# MAIN.net
KiCad netlist of a schematic drawn in Altium Designer
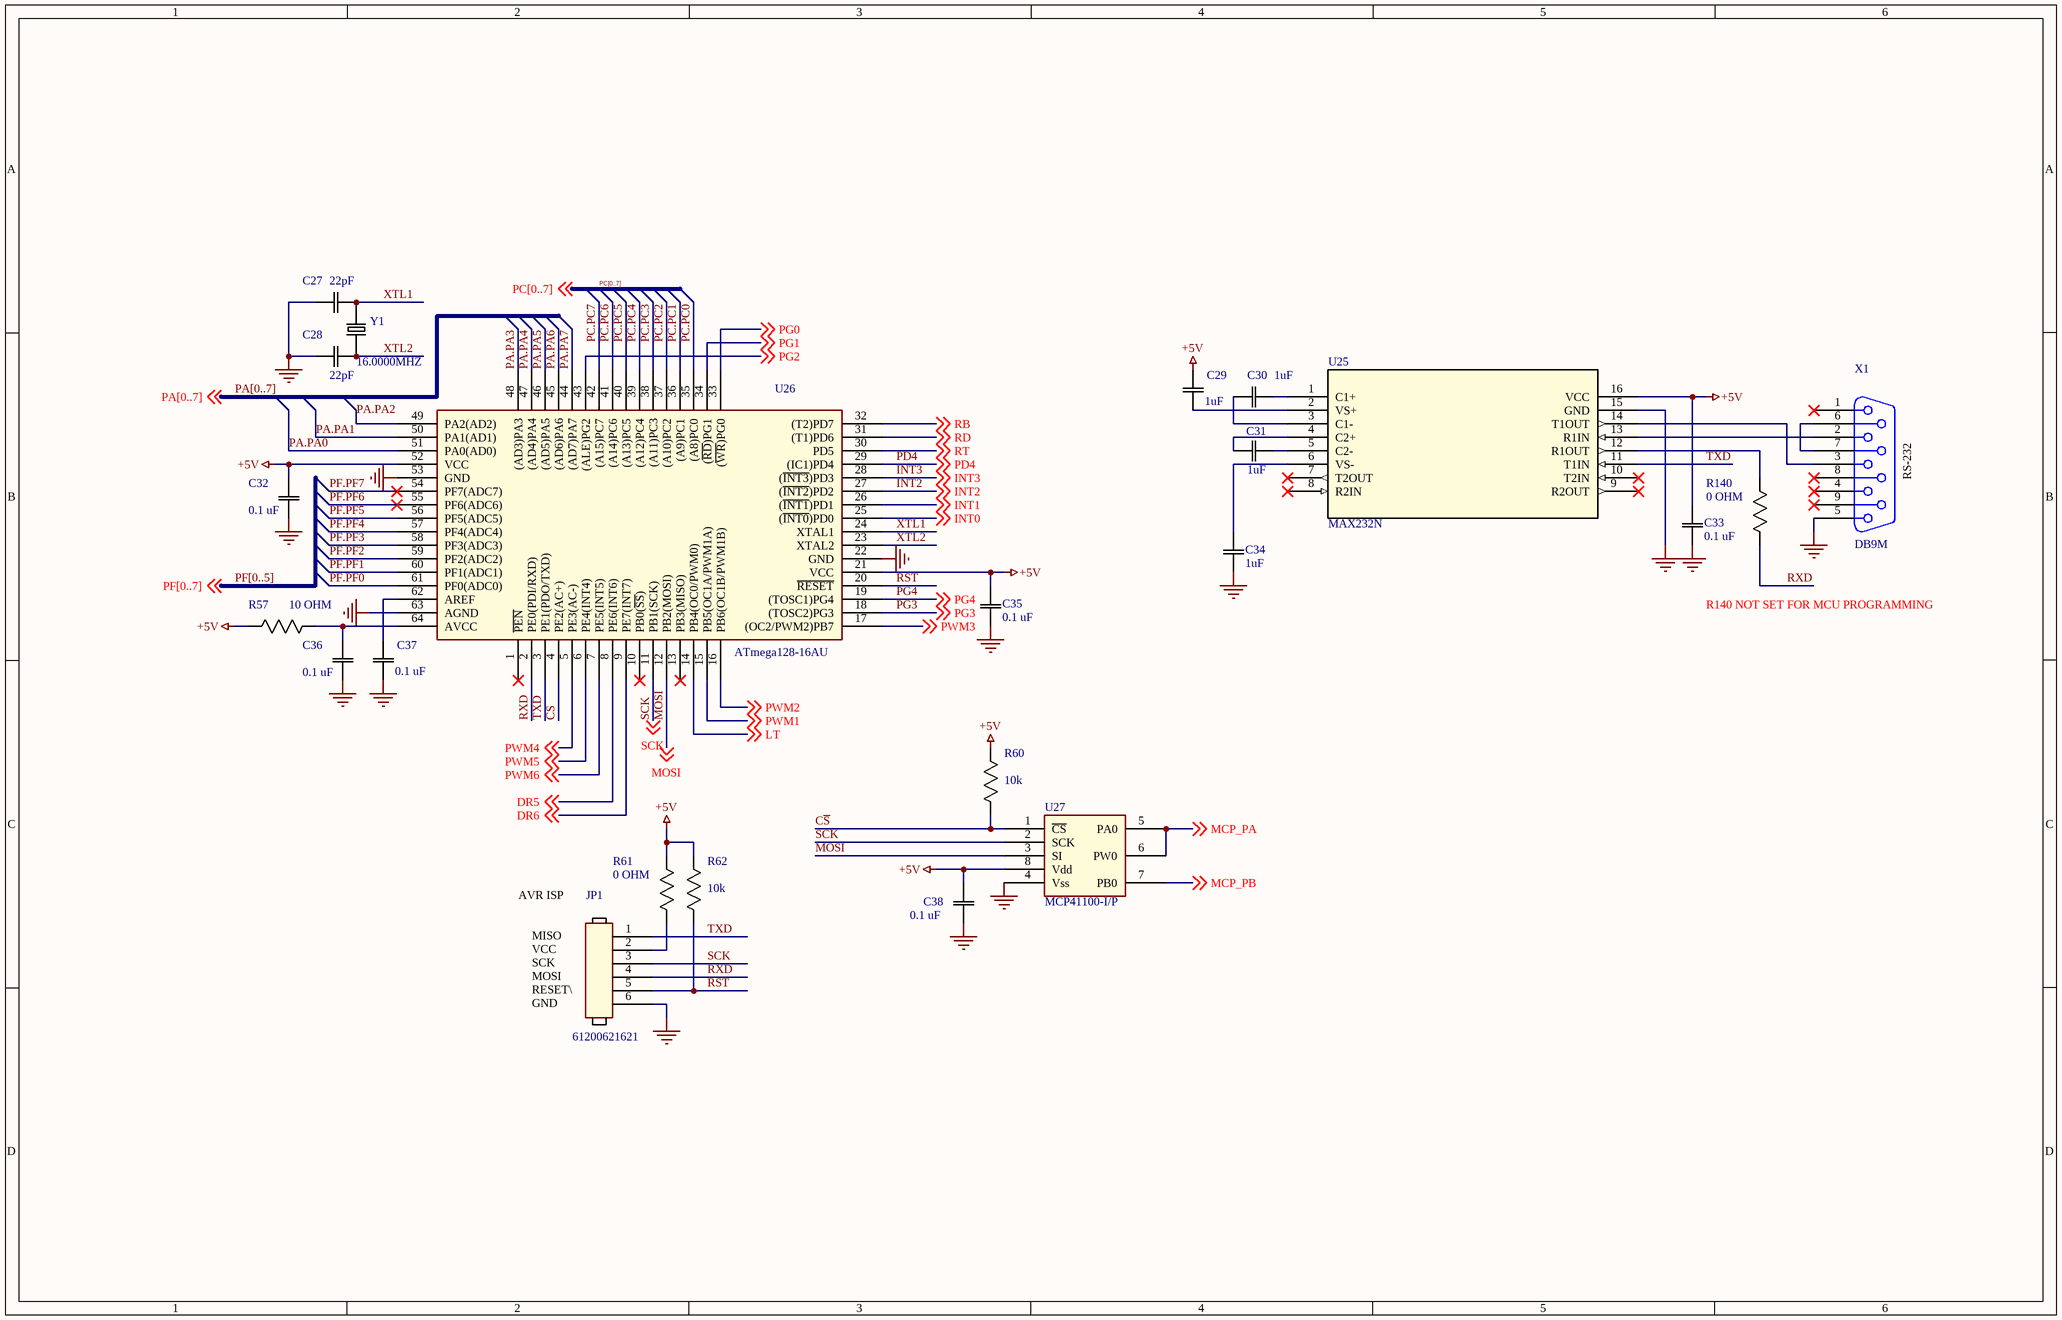
[diagram p0: MAIN.SchDoc]

(export (version "E")
  (design (tool "Eeschema 10.0.6"))
  (components
    (comp (ref "C27")
      (value "22pF")
      (footprint "SR20")
      (description "22pF ±5% 50V Ceramic Capacitor C0G, NP0 Radial")
      (fields (field (name "MANUFACTURER_PART_NUMBER") "C315C220J5G5TA"))
      (libsource (lib "Discrete") (part "CAP RADIAL 2.54"))
    )
    (comp (ref "C28")
      (value "22pF")
      (footprint "SR20")
      (description "22pF ±5% 50V Ceramic Capacitor C0G, NP0 Radial")
      (fields (field (name "MANUFACTURER_PART_NUMBER") "C315C220J5G5TA"))
      (libsource (lib "Discrete") (part "CAP RADIAL 2.54"))
    )
    (comp (ref "C29")
      (value "1uF")
      (footprint "SR20")
      (description "1µF ±10% 25V Ceramic Capacitor X7R Radial")
      (fields (field (name "MANUFACTURER_PART_NUMBER") "C315C105K3R5TA"))
      (libsource (lib "Discrete") (part "CAP RADIAL 2.54"))
    )
    (comp (ref "C30")
      (value "1uF")
      (footprint "SR20")
      (description "1µF ±10% 25V Ceramic Capacitor X7R Radial")
      (fields (field (name "MANUFACTURER_PART_NUMBER") "C315C105K3R5TA"))
      (libsource (lib "Discrete") (part "CAP RADIAL 2.54"))
    )
    (comp (ref "C31")
      (value "1uF")
      (footprint "SR20")
      (description "1µF ±10% 25V Ceramic Capacitor X7R Radial")
      (fields (field (name "MANUFACTURER_PART_NUMBER") "C315C105K3R5TA"))
      (libsource (lib "Discrete") (part "CAP RADIAL 2.54"))
    )
    (comp (ref "C32")
      (value "0.1 uF")
      (footprint "SR20")
      (description "0.1µF ±10% 100V Ceramic Capacitor X7R Radial")
      (fields (field (name "MANUFACTURER_PART_NUMBER") "C320C104K1R5TA7301"))
      (libsource (lib "Discrete") (part "CAP RADIAL 2.54"))
    )
    (comp (ref "C33")
      (value "0.1 uF")
      (footprint "SR20")
      (description "0.1µF ±10% 100V Ceramic Capacitor X7R Radial")
      (fields (field (name "MANUFACTURER_PART_NUMBER") "C320C104K1R5TA7301"))
      (libsource (lib "Discrete") (part "CAP RADIAL 2.54"))
    )
    (comp (ref "C34")
      (value "1uF")
      (footprint "SR20")
      (description "1µF ±10% 25V Ceramic Capacitor X7R Radial")
      (fields (field (name "MANUFACTURER_PART_NUMBER") "C315C105K3R5TA"))
      (libsource (lib "Discrete") (part "CAP RADIAL 2.54"))
    )
    (comp (ref "C35")
      (value "0.1 uF")
      (footprint "SR20")
      (description "0.1µF ±10% 100V Ceramic Capacitor X7R Radial")
      (fields (field (name "MANUFACTURER_PART_NUMBER") "C320C104K1R5TA7301"))
      (libsource (lib "Discrete") (part "CAP RADIAL 2.54"))
    )
    (comp (ref "C36")
      (value "0.1 uF")
      (footprint "SR20")
      (description "0.1µF ±10% 100V Ceramic Capacitor X7R Radial")
      (fields (field (name "MANUFACTURER_PART_NUMBER") "C320C104K1R5TA7301"))
      (libsource (lib "Discrete") (part "CAP RADIAL 2.54"))
    )
    (comp (ref "C37")
      (value "0.1 uF")
      (footprint "SR20")
      (description "0.1µF ±10% 100V Ceramic Capacitor X7R Radial")
      (fields (field (name "MANUFACTURER_PART_NUMBER") "C320C104K1R5TA7301"))
      (libsource (lib "Discrete") (part "CAP RADIAL 2.54"))
    )
    (comp (ref "C38")
      (value "0.1 uF")
      (footprint "SR20")
      (description "0.1µF ±10% 100V Ceramic Capacitor X7R Radial")
      (fields (field (name "MANUFACTURER_PART_NUMBER") "C320C104K1R5TA7301"))
      (libsource (lib "Discrete") (part "CAP RADIAL 2.54"))
    )
    (comp (ref "JP1")
      (value "61200621621")
      (footprint "BLKCON.100/VH/TM2OE/W.200/6")
      (description "Wire-To-Board Connector, WR-BHD Series, Through Hole, Header, 6, 2.54 mm, Gold Plated Contacts")
      (libsource (lib "*") (part "HEADER 6"))
    )
    (comp (ref "R57")
      (value "10 OHM")
      (footprint "RES AXIAL 1/6W")
      (description "RES 10 OHM 1/6W 5% AXIAL")
      (fields (field (name "MANUFACTURER_PART_NUMBER") "CFR-12JB-52-10R"))
      (libsource (lib "Discrete") (part "Resistor Axial  1/6W"))
    )
    (comp (ref "R60")
      (value "10k")
      (footprint "RES AXIAL 1/6W")
      (description "RES 10K OHM 1/6W 5% AXIAL")
      (fields (field (name "MANUFACTURER_PART_NUMBER") "CFR-12JB-52-10K"))
      (libsource (lib "Discrete") (part "Resistor Axial  1/6W"))
    )
    (comp (ref "R61")
      (value "0 OHM")
      (footprint "RES AXIAL 1/6W")
      (description "RES 0 OHM 1/6W JUMP AXIAL")
      (fields (field (name "MANUFACTURER_PART_NUMBER") "ZOR-12-B-52-0R"))
      (libsource (lib "Discrete") (part "Resistor Axial  1/6W"))
    )
    (comp (ref "R62")
      (value "10k")
      (footprint "RES AXIAL 1/6W")
      (description "RES 10K OHM 1/6W 5% AXIAL")
      (fields (field (name "MANUFACTURER_PART_NUMBER") "CFR-12JB-52-10K"))
      (libsource (lib "Discrete") (part "Resistor Axial  1/6W"))
    )
    (comp (ref "R140")
      (value "0 OHM")
      (footprint "RES AXIAL 1/6W")
      (description "RES 0 OHM 1/6W JUMP AXIAL")
      (fields (field (name "MANUFACTURER_PART_NUMBER") "ZOR-12-B-52-0R"))
      (libsource (lib "Discrete") (part "Resistor Axial  1/6W"))
    )
    (comp (ref "U25")
      (value "MAX232N")
      (footprint "N16")
      (description "Imported")
      (libsource (lib "ICs") (part "MAX232N"))
    )
    (comp (ref "U26")
      (value "ATmega128-16AU")
      (footprint "QUAD.80M/64/WG16.00")
      (libsource (lib "*") (part "ATMega103_1"))
    )
    (comp (ref "U27")
      (value "MCP41100-I/P")
      (footprint "*DIP254P762X508-8")
      (description "IC POT DGTL 100K 2CH SPI 14-DIP")
      (libsource (lib "ICs") (part "MCP41100-I/P"))
    )
    (comp (ref "X1")
      (value "DB9M")
      (footprint "DSUB/RP.318/TM/9")
      (libsource (lib "*") (part "CONNECTOR DB9"))
    )
    (comp (ref "Y1")
      (value "16.0000MHZ")
      (footprint "HC-49/US")
      (description "16MHz ±30ppm Crystal 20pF 40 Ohms HC-49/US")
      (fields (field (name "MANUFACTURER_PART_NUMBER") "ECS-160-20-4X"))
      (libsource (lib "Discrete") (part "CRYSTAL HC-49/US"))
    )
  )
  (nets
    (net (code "1") (name "+5V") (class "Default")
      (node (ref "C29") (pin "1") (pinfunction "1_1") (pintype "passive"))
      (node (ref "C32") (pin "2") (pinfunction "2_2") (pintype "passive"))
      (node (ref "C33") (pin "2") (pinfunction "2_2") (pintype "passive"))
      (node (ref "C35") (pin "2") (pinfunction "2_2") (pintype "passive"))
      (node (ref "C38") (pin "2") (pinfunction "2_2") (pintype "passive"))
      (node (ref "R57") (pin "2") (pinfunction "2_2") (pintype "passive"))
      (node (ref "R60") (pin "2") (pinfunction "2_2") (pintype "passive"))
      (node (ref "R61") (pin "2") (pinfunction "2_2") (pintype "passive"))
      (node (ref "R62") (pin "2") (pinfunction "2_2") (pintype "passive"))
      (node (ref "U25") (pin "16") (pinfunction "VCC_16") (pintype "power_in"))
      (node (ref "U26") (pin "21") (pinfunction "VCC_21") (pintype "power_in"))
      (node (ref "U26") (pin "52") (pinfunction "VCC_52") (pintype "power_in"))
      (node (ref "U27") (pin "8") (pinfunction "Vdd_8") (pintype "passive"))
    )
    (net (code "2") (name "/C~{S}") (class "Default")
      (node (ref "R60") (pin "1") (pinfunction "1_1") (pintype "passive"))
      (node (ref "U26") (pin "4") (pinfunction "PE2(AC+)_4") (pintype "passive"))
      (node (ref "U27") (pin "1") (pinfunction "~{CS}_1") (pintype "passive"))
    )
    (net (code "3") (name "/PA.PA0") (class "Default")
      (node (ref "U26") (pin "51") (pinfunction "PA0(AD0)_51") (pintype "passive"))
    )
    (net (code "4") (name "/PA.PA1") (class "Default")
      (node (ref "U26") (pin "50") (pinfunction "PA1(AD1)_50") (pintype "passive"))
    )
    (net (code "5") (name "/PA.PA2") (class "Default")
      (node (ref "U26") (pin "49") (pinfunction "PA2(AD2)_49") (pintype "passive"))
    )
    (net (code "6") (name "/PA.PA3") (class "Default")
      (node (ref "U26") (pin "48") (pinfunction "(AD3)PA3_48") (pintype "passive"))
    )
    (net (code "7") (name "/PA.PA4") (class "Default")
      (node (ref "U26") (pin "47") (pinfunction "(AD4)PA4_47") (pintype "passive"))
    )
    (net (code "8") (name "/PA.PA5") (class "Default")
      (node (ref "U26") (pin "46") (pinfunction "(AD5)PA5_46") (pintype "passive"))
    )
    (net (code "9") (name "/PA.PA6") (class "Default")
      (node (ref "U26") (pin "45") (pinfunction "(AD6)PA6_45") (pintype "passive"))
    )
    (net (code "10") (name "/PA.PA7") (class "Default")
      (node (ref "U26") (pin "44") (pinfunction "(AD7)PA7_44") (pintype "passive"))
    )
    (net (code "11") (name "/PC.PC0") (class "Default")
      (node (ref "U26") (pin "35") (pinfunction "(A8)PC0_35") (pintype "passive"))
    )
    (net (code "12") (name "/PC.PC1") (class "Default")
      (node (ref "U26") (pin "36") (pinfunction "(A9)PC1_36") (pintype "passive"))
    )
    (net (code "13") (name "/PC.PC2") (class "Default")
      (node (ref "U26") (pin "37") (pinfunction "(A10)PC2_37") (pintype "passive"))
    )
    (net (code "14") (name "/PC.PC3") (class "Default")
      (node (ref "U26") (pin "38") (pinfunction "(A11)PC3_38") (pintype "passive"))
    )
    (net (code "15") (name "/PC.PC4") (class "Default")
      (node (ref "U26") (pin "39") (pinfunction "(A12)PC4_39") (pintype "passive"))
    )
    (net (code "16") (name "/PC.PC5") (class "Default")
      (node (ref "U26") (pin "40") (pinfunction "(A13)PC5_40") (pintype "passive"))
    )
    (net (code "17") (name "/PC.PC6") (class "Default")
      (node (ref "U26") (pin "41") (pinfunction "(A14)PC6_41") (pintype "passive"))
    )
    (net (code "18") (name "/PC.PC7") (class "Default")
      (node (ref "U26") (pin "42") (pinfunction "(A15)PC7_42") (pintype "passive"))
    )
    (net (code "19") (name "/PF.PF0") (class "Default")
      (node (ref "U26") (pin "61") (pinfunction "PF0(ADC0)_61") (pintype "passive"))
    )
    (net (code "20") (name "/PF.PF1") (class "Default")
      (node (ref "U26") (pin "60") (pinfunction "PF1(ADC1)_60") (pintype "passive"))
    )
    (net (code "21") (name "/PF.PF2") (class "Default")
      (node (ref "U26") (pin "59") (pinfunction "PF2(ADC2)_59") (pintype "passive"))
    )
    (net (code "22") (name "/PF.PF3") (class "Default")
      (node (ref "U26") (pin "58") (pinfunction "PF3(ADC3)_58") (pintype "passive"))
    )
    (net (code "23") (name "/PF.PF4") (class "Default")
      (node (ref "U26") (pin "57") (pinfunction "PF4(ADC4)_57") (pintype "passive"))
    )
    (net (code "24") (name "/PF.PF5") (class "Default")
      (node (ref "U26") (pin "56") (pinfunction "PF5(ADC5)_56") (pintype "passive"))
    )
    (net (code "25") (name "/PF.PF6") (class "Default")
      (node (ref "U26") (pin "55") (pinfunction "PF6(ADC6)_55") (pintype "passive+no_connect"))
    )
    (net (code "26") (name "/PF.PF7") (class "Default")
      (node (ref "U26") (pin "54") (pinfunction "PF7(ADC7)_54") (pintype "passive+no_connect"))
    )
    (net (code "27") (name "/RS~{T}") (class "Default")
      (node (ref "JP1") (pin "5") (pinfunction "5_5") (pintype "passive"))
      (node (ref "R62") (pin "1") (pinfunction "1_1") (pintype "passive"))
      (node (ref "U26") (pin "20") (pinfunction "~{RESET}_20") (pintype "passive"))
    )
    (net (code "28") (name "/RXD") (class "Default")
      (node (ref "JP1") (pin "4") (pinfunction "4_4") (pintype "passive"))
      (node (ref "R140") (pin "1") (pinfunction "1_1") (pintype "passive"))
      (node (ref "U26") (pin "2") (pinfunction "PE0(PDI/RXD)_2") (pintype "passive"))
    )
    (net (code "29") (name "/TXD") (class "Default")
      (node (ref "JP1") (pin "1") (pinfunction "1_1") (pintype "passive"))
      (node (ref "U25") (pin "11") (pinfunction "T1IN_11") (pintype "input"))
      (node (ref "U26") (pin "3") (pinfunction "PE1(PDO/TXD)_3") (pintype "passive"))
    )
    (net (code "30") (name "/XTL1") (class "Default")
      (node (ref "C27") (pin "2") (pinfunction "2_2") (pintype "passive"))
      (node (ref "U26") (pin "24") (pinfunction "XTAL1_24") (pintype "passive"))
      (node (ref "Y1") (pin "1") (pinfunction "1_1") (pintype "passive"))
    )
    (net (code "31") (name "/XTL2") (class "Default")
      (node (ref "C28") (pin "2") (pinfunction "2_2") (pintype "passive"))
      (node (ref "U26") (pin "23") (pinfunction "XTAL2_23") (pintype "passive"))
      (node (ref "Y1") (pin "2") (pinfunction "2_2") (pintype "passive"))
    )
    (net (code "32") (name "DR5") (class "Default")
      (node (ref "U26") (pin "8") (pinfunction "PE6(INT6)_8") (pintype "passive"))
    )
    (net (code "33") (name "DR6") (class "Default")
      (node (ref "U26") (pin "9") (pinfunction "PE7(INT7)_9") (pintype "passive"))
    )
    (net (code "34") (name "GND") (class "Default")
      (node (ref "C27") (pin "1") (pinfunction "1_1") (pintype "passive"))
      (node (ref "C28") (pin "1") (pinfunction "1_1") (pintype "passive"))
      (node (ref "C32") (pin "1") (pinfunction "1_1") (pintype "passive"))
      (node (ref "C33") (pin "1") (pinfunction "1_1") (pintype "passive"))
      (node (ref "C34") (pin "2") (pinfunction "2_2") (pintype "passive"))
      (node (ref "C35") (pin "1") (pinfunction "1_1") (pintype "passive"))
      (node (ref "C36") (pin "1") (pinfunction "1_1") (pintype "passive"))
      (node (ref "C37") (pin "1") (pinfunction "1_1") (pintype "passive"))
      (node (ref "C38") (pin "1") (pinfunction "1_1") (pintype "passive"))
      (node (ref "JP1") (pin "6") (pinfunction "6_6") (pintype "passive"))
      (node (ref "U25") (pin "15") (pinfunction "GND_15") (pintype "power_in"))
      (node (ref "U26") (pin "22") (pinfunction "GND_22") (pintype "power_in"))
      (node (ref "U26") (pin "53") (pinfunction "GND_53") (pintype "power_in"))
      (node (ref "U26") (pin "63") (pinfunction "AGND_63") (pintype "passive"))
      (node (ref "U27") (pin "4") (pinfunction "Vss_4") (pintype "passive"))
      (node (ref "X1") (pin "5") (pinfunction "5_5") (pintype "passive"))
    )
    (net (code "35") (name "INT0") (class "Default")
      (node (ref "U26") (pin "25") (pinfunction "(~{INT0})PD0_25") (pintype "passive"))
    )
    (net (code "36") (name "INT1") (class "Default")
      (node (ref "U26") (pin "26") (pinfunction "(~{INT1})PD1_26") (pintype "passive"))
    )
    (net (code "37") (name "INT2") (class "Default")
      (node (ref "U26") (pin "27") (pinfunction "(~{INT2})PD2_27") (pintype "passive"))
    )
    (net (code "38") (name "INT3") (class "Default")
      (node (ref "U26") (pin "28") (pinfunction "(~{INT3})PD3_28") (pintype "passive"))
    )
    (net (code "39") (name "LT") (class "Default")
      (node (ref "U26") (pin "14") (pinfunction "PB4(OC0/PWM0)_14") (pintype "passive"))
    )
    (net (code "40") (name "MCP_PA") (class "Default")
      (node (ref "U27") (pin "5") (pinfunction "PA0_5") (pintype "passive"))
      (node (ref "U27") (pin "6") (pinfunction "PW0_6") (pintype "passive"))
    )
    (net (code "41") (name "MCP_PB") (class "Default")
      (node (ref "U27") (pin "7") (pinfunction "PB0_7") (pintype "passive"))
    )
    (net (code "42") (name "MOSI") (class "Default")
      (node (ref "U26") (pin "12") (pinfunction "PB2(MOSI)_12") (pintype "passive"))
      (node (ref "U27") (pin "3") (pinfunction "SI_3") (pintype "passive"))
    )
    (net (code "43") (name "Net-(JP1-Pad2)") (class "Default")
      (node (ref "JP1") (pin "2") (pinfunction "2_2") (pintype "passive"))
      (node (ref "R61") (pin "1") (pinfunction "1_1") (pintype "passive"))
    )
    (net (code "44") (name "Net-(U25-C1+)") (class "Default")
      (node (ref "C30") (pin "1") (pinfunction "1_1") (pintype "passive"))
      (node (ref "U25") (pin "1") (pinfunction "C1+_1") (pintype "passive"))
    )
    (net (code "45") (name "Net-(U25-C1-)") (class "Default")
      (node (ref "C30") (pin "2") (pinfunction "2_2") (pintype "passive"))
      (node (ref "U25") (pin "3") (pinfunction "C1-_3") (pintype "passive"))
    )
    (net (code "46") (name "Net-(U25-C2+)") (class "Default")
      (node (ref "C31") (pin "2") (pinfunction "2_2") (pintype "passive"))
      (node (ref "U25") (pin "4") (pinfunction "C2+_4") (pintype "passive"))
    )
    (net (code "47") (name "Net-(U25-C2-)") (class "Default")
      (node (ref "C31") (pin "1") (pinfunction "1_1") (pintype "passive"))
      (node (ref "U25") (pin "5") (pinfunction "C2-_5") (pintype "passive"))
    )
    (net (code "48") (name "Net-(U25-R1IN)") (class "Default")
      (node (ref "U25") (pin "13") (pinfunction "R1IN_13") (pintype "input"))
      (node (ref "X1") (pin "2") (pinfunction "2_2") (pintype "passive"))
    )
    (net (code "49") (name "Net-(U25-R1OUT)") (class "Default")
      (node (ref "R140") (pin "2") (pinfunction "2_2") (pintype "passive"))
      (node (ref "U25") (pin "12") (pinfunction "R1OUT_12") (pintype "output"))
    )
    (net (code "50") (name "Net-(U25-T1OUT)") (class "Default")
      (node (ref "U25") (pin "14") (pinfunction "T1OUT_14") (pintype "output"))
      (node (ref "X1") (pin "3") (pinfunction "3_3") (pintype "passive"))
    )
    (net (code "51") (name "Net-(U25-VS+)") (class "Default")
      (node (ref "C29") (pin "2") (pinfunction "2_2") (pintype "passive"))
      (node (ref "U25") (pin "2") (pinfunction "VS+_2") (pintype "power_in"))
    )
    (net (code "52") (name "Net-(U25-VS-)") (class "Default")
      (node (ref "C34") (pin "1") (pinfunction "1_1") (pintype "passive"))
      (node (ref "U25") (pin "6") (pinfunction "VS-_6") (pintype "power_in"))
    )
    (net (code "53") (name "Net-(U26-AREF)") (class "Default")
      (node (ref "C37") (pin "2") (pinfunction "2_2") (pintype "passive"))
      (node (ref "U26") (pin "62") (pinfunction "AREF_62") (pintype "passive"))
    )
    (net (code "54") (name "Net-(U26-AVCC)") (class "Default")
      (node (ref "C36") (pin "2") (pinfunction "2_2") (pintype "passive"))
      (node (ref "R57") (pin "1") (pinfunction "1_1") (pintype "passive"))
      (node (ref "U26") (pin "64") (pinfunction "AVCC_64") (pintype "passive"))
    )
    (net (code "55") (name "Net-(X1-Pad6)") (class "Default")
      (node (ref "X1") (pin "6") (pinfunction "6_6") (pintype "passive"))
      (node (ref "X1") (pin "7") (pinfunction "7_7") (pintype "passive"))
    )
    (net (code "58") (name "PD4") (class "Default")
      (node (ref "U26") (pin "29") (pinfunction "(IC1)PD4_29") (pintype "passive"))
    )
    (net (code "60") (name "PG0") (class "Default")
      (node (ref "U26") (pin "33") (pinfunction "(~{WR})PG0_33") (pintype "passive"))
    )
    (net (code "61") (name "PG1") (class "Default")
      (node (ref "U26") (pin "34") (pinfunction "(~{RD})PG1_34") (pintype "passive"))
    )
    (net (code "62") (name "PG2") (class "Default")
      (node (ref "U26") (pin "43") (pinfunction "(ALE)PG2_43") (pintype "passive"))
    )
    (net (code "63") (name "PG3") (class "Default")
      (node (ref "U26") (pin "18") (pinfunction "(TOSC2)PG3_18") (pintype "passive"))
    )
    (net (code "64") (name "PG4") (class "Default")
      (node (ref "U26") (pin "19") (pinfunction "(TOSC1)PG4_19") (pintype "passive"))
    )
    (net (code "65") (name "PWM1") (class "Default")
      (node (ref "U26") (pin "15") (pinfunction "PB5(OC1A/PWM1A)_15") (pintype "passive"))
    )
    (net (code "66") (name "PWM2") (class "Default")
      (node (ref "U26") (pin "16") (pinfunction "PB6(OC1B/PWM1B)_16") (pintype "passive"))
    )
    (net (code "67") (name "PWM3") (class "Default")
      (node (ref "U26") (pin "17") (pinfunction "(OC2/PWM2)PB7_17") (pintype "passive"))
    )
    (net (code "68") (name "PWM4") (class "Default")
      (node (ref "U26") (pin "5") (pinfunction "PE3(AC-)_5") (pintype "passive"))
    )
    (net (code "69") (name "PWM5") (class "Default")
      (node (ref "U26") (pin "6") (pinfunction "PE4(INT4)_6") (pintype "passive"))
    )
    (net (code "70") (name "PWM6") (class "Default")
      (node (ref "U26") (pin "7") (pinfunction "PE5(INT5)_7") (pintype "passive"))
    )
    (net (code "71") (name "RB") (class "Default")
      (node (ref "U26") (pin "32") (pinfunction "(T2)PD7_32") (pintype "passive"))
    )
    (net (code "72") (name "RD") (class "Default")
      (node (ref "U26") (pin "31") (pinfunction "(T1)PD6_31") (pintype "passive"))
    )
    (net (code "73") (name "RT") (class "Default")
      (node (ref "U26") (pin "30") (pinfunction "PD5_30") (pintype "passive"))
    )
    (net (code "74") (name "SCK") (class "Default")
      (node (ref "JP1") (pin "3") (pinfunction "3_3") (pintype "passive"))
      (node (ref "U26") (pin "11") (pinfunction "PB1(SCK)_11") (pintype "passive"))
      (node (ref "U27") (pin "2") (pinfunction "SCK_2") (pintype "passive"))
    )
    (net (code "75") (name "unconnected-(U25-R2IN-Pad8)") (class "Default")
      (node (ref "U25") (pin "8") (pinfunction "R2IN_8") (pintype "input+no_connect"))
    )
    (net (code "76") (name "unconnected-(U25-R2OUT-Pad9)") (class "Default")
      (node (ref "U25") (pin "9") (pinfunction "R2OUT_9") (pintype "output+no_connect"))
    )
    (net (code "77") (name "unconnected-(U25-T2IN-Pad10)") (class "Default")
      (node (ref "U25") (pin "10") (pinfunction "T2IN_10") (pintype "input+no_connect"))
    )
    (net (code "78") (name "unconnected-(U25-T2OUT-Pad7)") (class "Default")
      (node (ref "U25") (pin "7") (pinfunction "T2OUT_7") (pintype "output+no_connect"))
    )
    (net (code "79") (name "unconnected-(U26-PB0(~{SS})-Pad10)") (class "Default")
      (node (ref "U26") (pin "10") (pinfunction "PB0(~{SS})_10") (pintype "passive+no_connect"))
    )
    (net (code "80") (name "unconnected-(U26-PB3(MISO)-Pad13)") (class "Default")
      (node (ref "U26") (pin "13") (pinfunction "PB3(MISO)_13") (pintype "passive+no_connect"))
    )
    (net (code "81") (name "unconnected-(U26-~{PEN}-Pad1)") (class "Default")
      (node (ref "U26") (pin "1") (pinfunction "~{PEN}_1") (pintype "passive+no_connect"))
    )
    (net (code "82") (name "unconnected-(X1-Pad1)") (class "Default")
      (node (ref "X1") (pin "1") (pinfunction "1_1") (pintype "passive+no_connect"))
    )
    (net (code "83") (name "unconnected-(X1-Pad4)") (class "Default")
      (node (ref "X1") (pin "4") (pinfunction "4_4") (pintype "passive+no_connect"))
    )
    (net (code "84") (name "unconnected-(X1-Pad8)") (class "Default")
      (node (ref "X1") (pin "8") (pinfunction "8_8") (pintype "passive+no_connect"))
    )
    (net (code "85") (name "unconnected-(X1-Pad9)") (class "Default")
      (node (ref "X1") (pin "9") (pinfunction "9_9") (pintype "passive+no_connect"))
    )
  )
)
